# PIC32_NVME.net
KiCad netlist of a schematic drawn in Altium Designer
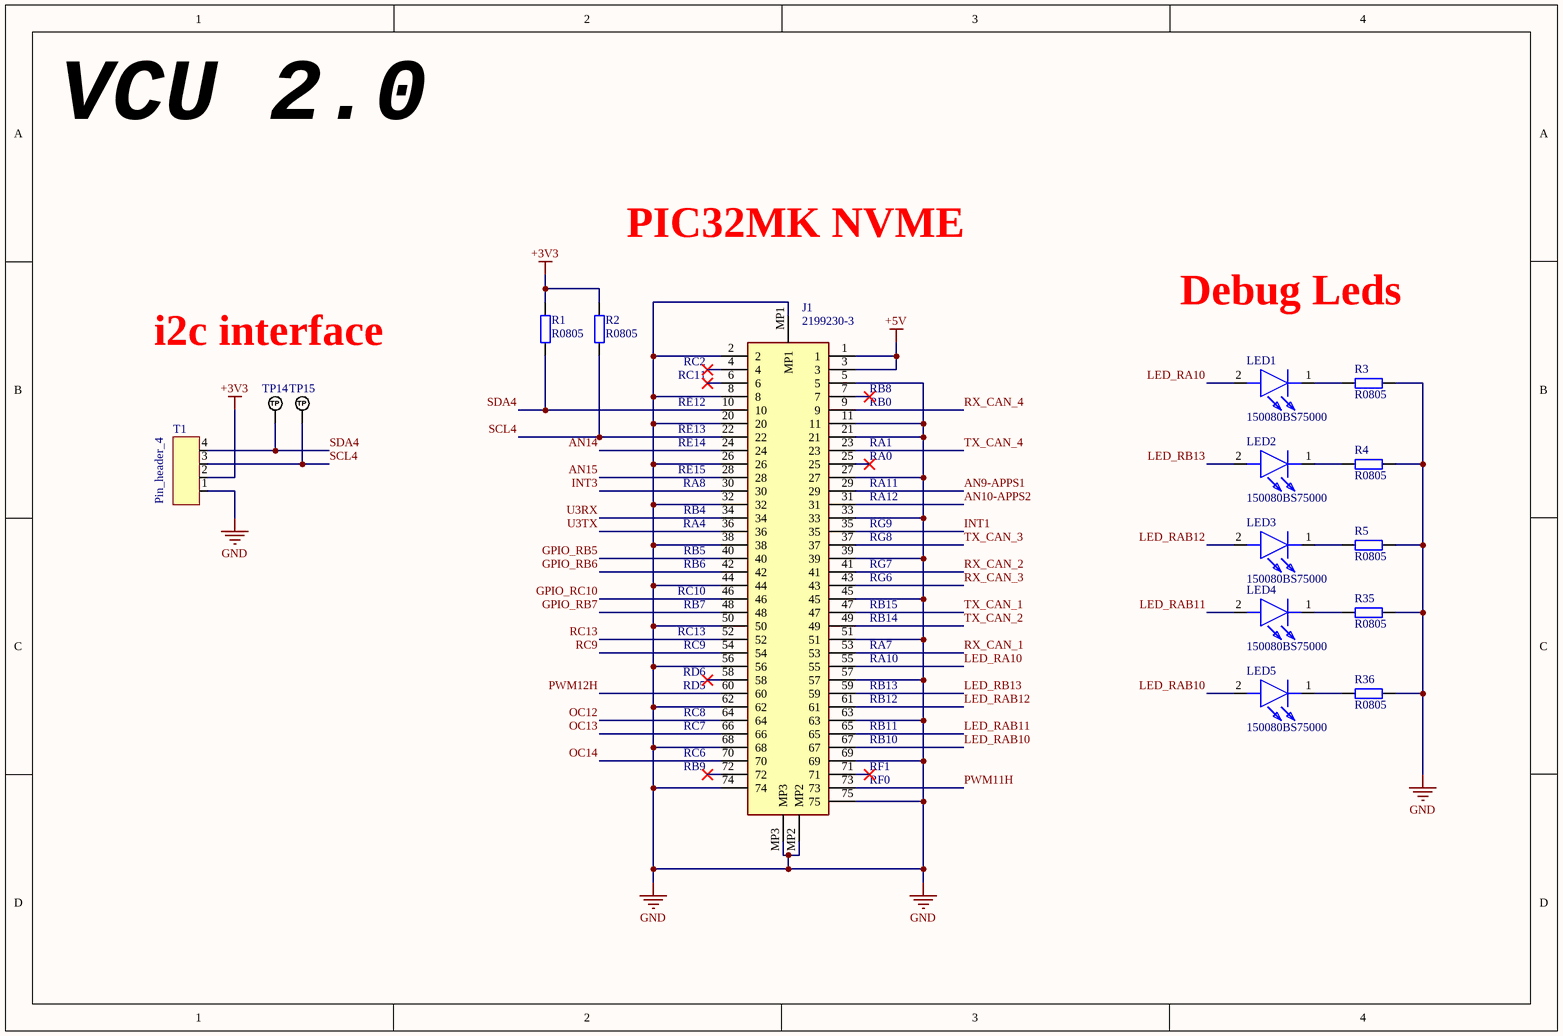
[diagram p0: PIC32_NVME.SchDoc]

(export (version "E")
  (design (tool "Eeschema 10.0.6"))
  (components
    (comp (ref "J1")
      (value "2199230-3")
      (footprint "21992303")
      (description "Connector")
      (fields (field (name "MOUSER PART NUMBER") "571-2199230-3"))
      (libsource (lib "Pedro_Integrated_Library") (part "2199230-3"))
    )
    (comp (ref "LED1")
      (value "150080BS75000")
      (footprint "LEDC2012X80N")
      (description "LED")
      (fields (field (name "MOUSER PART NUMBER") "710-150080BS75000"))
      (libsource (lib "Pedro_Integrated_Library") (part "150080BS75000"))
    )
    (comp (ref "LED2")
      (value "150080BS75000")
      (footprint "LEDC2012X80N")
      (description "LED")
      (fields (field (name "MOUSER PART NUMBER") "710-150080BS75000"))
      (libsource (lib "Pedro_Integrated_Library") (part "150080BS75000"))
    )
    (comp (ref "LED3")
      (value "150080BS75000")
      (footprint "LEDC2012X80N")
      (description "LED")
      (fields (field (name "MOUSER PART NUMBER") "710-150080BS75000"))
      (libsource (lib "Pedro_Integrated_Library") (part "150080BS75000"))
    )
    (comp (ref "LED4")
      (value "150080BS75000")
      (footprint "LEDC2012X80N")
      (description "LED")
      (fields (field (name "MOUSER PART NUMBER") "710-150080BS75000"))
      (libsource (lib "Pedro_Integrated_Library") (part "150080BS75000"))
    )
    (comp (ref "LED5")
      (value "150080BS75000")
      (footprint "LEDC2012X80N")
      (description "LED")
      (fields (field (name "MOUSER PART NUMBER") "710-150080BS75000"))
      (libsource (lib "Pedro_Integrated_Library") (part "150080BS75000"))
    )
    (comp (ref "R1")
      (value "R0805")
      (footprint "RES_0805")
      (description "Resistor SMD 0805")
      (libsource (lib "Schematic-Lib-PhilsLab") (part "RES_0805"))
    )
    (comp (ref "R2")
      (value "R0805")
      (footprint "RES_0805")
      (description "Resistor SMD 0805")
      (libsource (lib "Schematic-Lib-PhilsLab") (part "RES_0805"))
    )
    (comp (ref "R3")
      (value "R0805")
      (footprint "RES_0805")
      (description "Resistor SMD 0805")
      (libsource (lib "Schematic-Lib-PhilsLab") (part "RES_0805"))
    )
    (comp (ref "R4")
      (value "R0805")
      (footprint "RES_0805")
      (description "Resistor SMD 0805")
      (libsource (lib "Schematic-Lib-PhilsLab") (part "RES_0805"))
    )
    (comp (ref "R5")
      (value "R0805")
      (footprint "RES_0805")
      (description "Resistor SMD 0805")
      (libsource (lib "Schematic-Lib-PhilsLab") (part "RES_0805"))
    )
    (comp (ref "R35")
      (value "R0805")
      (footprint "RES_0805")
      (description "Resistor SMD 0805")
      (libsource (lib "Schematic-Lib-PhilsLab") (part "RES_0805"))
    )
    (comp (ref "R36")
      (value "R0805")
      (footprint "RES_0805")
      (description "Resistor SMD 0805")
      (libsource (lib "Schematic-Lib-PhilsLab") (part "RES_0805"))
    )
    (comp (ref "T1")
      (value "Pin_header_4")
      (footprint "Pin_header_4")
      (libsource (lib "Pedro_Integrated_Library") (part "Pin_header_4"))
    )
    (comp (ref "TP14")
      (value "TP_NOBOM")
      (footprint "PAD_RND_1MM")
      (description "Test Point Round 1mm (NO BOM)")
      (libsource (lib "Schematic-Lib-PhilsLab") (part "TEST_POINT_RND_1MM"))
    )
    (comp (ref "TP15")
      (value "TP_NOBOM")
      (footprint "PAD_RND_1MM")
      (description "Test Point Round 1mm (NO BOM)")
      (libsource (lib "Schematic-Lib-PhilsLab") (part "TEST_POINT_RND_1MM"))
    )
  )
  (nets
    (net (code "1") (name "+3V3") (class "Default")
      (node (ref "R1") (pin "1") (pinfunction "1_1") (pintype "passive"))
      (node (ref "R2") (pin "1") (pinfunction "1_1") (pintype "passive"))
      (node (ref "T1") (pin "2") (pintype "bidirectional"))
    )
    (net (code "2") (name "+5V") (class "Default")
      (node (ref "J1") (pin "1") (pinfunction "1_1") (pintype "passive"))
      (node (ref "J1") (pin "3") (pinfunction "3_3") (pintype "passive"))
    )
    (net (code "3") (name "/AN9-APPS1") (class "Default")
      (node (ref "J1") (pin "29") (pinfunction "29_29") (pintype "passive"))
    )
    (net (code "4") (name "/AN10-APPS2") (class "Default")
      (node (ref "J1") (pin "31") (pinfunction "31_31") (pintype "passive"))
    )
    (net (code "5") (name "/AN14") (class "Default")
      (node (ref "J1") (pin "24") (pinfunction "24_24") (pintype "passive"))
    )
    (net (code "6") (name "/AN15") (class "Default")
      (node (ref "J1") (pin "28") (pinfunction "28_28") (pintype "passive"))
    )
    (net (code "7") (name "/GPIO_RB5") (class "Default")
      (node (ref "J1") (pin "40") (pinfunction "40_40") (pintype "passive"))
    )
    (net (code "8") (name "/GPIO_RB6") (class "Default")
      (node (ref "J1") (pin "42") (pinfunction "42_42") (pintype "passive"))
    )
    (net (code "9") (name "/GPIO_RB7") (class "Default")
      (node (ref "J1") (pin "48") (pinfunction "48_48") (pintype "passive"))
    )
    (net (code "10") (name "/GPIO_RC10") (class "Default")
      (node (ref "J1") (pin "46") (pinfunction "46_46") (pintype "passive"))
    )
    (net (code "11") (name "/INT1") (class "Default")
      (node (ref "J1") (pin "35") (pinfunction "35_35") (pintype "passive"))
    )
    (net (code "12") (name "/INT3") (class "Default")
      (node (ref "J1") (pin "30") (pinfunction "30_30") (pintype "passive"))
    )
    (net (code "13") (name "/LED_RA10") (class "Default")
      (node (ref "J1") (pin "55") (pinfunction "55_55") (pintype "passive"))
      (node (ref "LED1") (pin "2") (pinfunction "A_2") (pintype "passive"))
    )
    (net (code "14") (name "/LED_RAB10") (class "Default")
      (node (ref "J1") (pin "67") (pinfunction "67_67") (pintype "passive"))
      (node (ref "LED5") (pin "2") (pinfunction "A_2") (pintype "passive"))
    )
    (net (code "15") (name "/LED_RAB11") (class "Default")
      (node (ref "J1") (pin "65") (pinfunction "65_65") (pintype "passive"))
      (node (ref "LED4") (pin "2") (pinfunction "A_2") (pintype "passive"))
    )
    (net (code "16") (name "/LED_RAB12") (class "Default")
      (node (ref "J1") (pin "61") (pinfunction "61_61") (pintype "passive"))
      (node (ref "LED3") (pin "2") (pinfunction "A_2") (pintype "passive"))
    )
    (net (code "17") (name "/LED_RB13") (class "Default")
      (node (ref "J1") (pin "59") (pinfunction "59_59") (pintype "passive"))
      (node (ref "LED2") (pin "2") (pinfunction "A_2") (pintype "passive"))
    )
    (net (code "18") (name "/OC12") (class "Default")
      (node (ref "J1") (pin "64") (pinfunction "64_64") (pintype "passive"))
    )
    (net (code "19") (name "/OC13") (class "Default")
      (node (ref "J1") (pin "66") (pinfunction "66_66") (pintype "passive"))
    )
    (net (code "20") (name "/OC14") (class "Default")
      (node (ref "J1") (pin "70") (pinfunction "70_70") (pintype "passive"))
    )
    (net (code "21") (name "/PWM11H") (class "Default")
      (node (ref "J1") (pin "73") (pinfunction "73_73") (pintype "passive"))
    )
    (net (code "22") (name "/PWM12H") (class "Default")
      (node (ref "J1") (pin "60") (pinfunction "60_60") (pintype "passive"))
    )
    (net (code "23") (name "/RC9") (class "Default")
      (node (ref "J1") (pin "54") (pinfunction "54_54") (pintype "passive"))
    )
    (net (code "24") (name "/RC13") (class "Default")
      (node (ref "J1") (pin "52") (pinfunction "52_52") (pintype "passive"))
    )
    (net (code "25") (name "/RX_CAN_1") (class "Default")
      (node (ref "J1") (pin "53") (pinfunction "53_53") (pintype "passive"))
    )
    (net (code "26") (name "/RX_CAN_2") (class "Default")
      (node (ref "J1") (pin "41") (pinfunction "41_41") (pintype "passive"))
    )
    (net (code "27") (name "/RX_CAN_3") (class "Default")
      (node (ref "J1") (pin "43") (pinfunction "43_43") (pintype "passive"))
    )
    (net (code "28") (name "/RX_CAN_4") (class "Default")
      (node (ref "J1") (pin "9") (pinfunction "9_9") (pintype "passive"))
    )
    (net (code "29") (name "/SCL4") (class "Default")
      (node (ref "J1") (pin "22") (pinfunction "22_22") (pintype "passive"))
      (node (ref "R2") (pin "2") (pinfunction "2_2") (pintype "passive"))
      (node (ref "T1") (pin "3") (pintype "bidirectional"))
      (node (ref "TP15") (pin "1") (pinfunction "TP_1") (pintype "passive"))
    )
    (net (code "30") (name "/SDA4") (class "Default")
      (node (ref "J1") (pin "10") (pinfunction "10_10") (pintype "passive"))
      (node (ref "R1") (pin "2") (pinfunction "2_2") (pintype "passive"))
      (node (ref "T1") (pin "4") (pintype "bidirectional"))
      (node (ref "TP14") (pin "1") (pinfunction "TP_1") (pintype "passive"))
    )
    (net (code "31") (name "/TX_CAN_1") (class "Default")
      (node (ref "J1") (pin "47") (pinfunction "47_47") (pintype "passive"))
    )
    (net (code "32") (name "/TX_CAN_2") (class "Default")
      (node (ref "J1") (pin "49") (pinfunction "49_49") (pintype "passive"))
    )
    (net (code "33") (name "/TX_CAN_3") (class "Default")
      (node (ref "J1") (pin "37") (pinfunction "37_37") (pintype "passive"))
    )
    (net (code "34") (name "/TX_CAN_4") (class "Default")
      (node (ref "J1") (pin "23") (pinfunction "23_23") (pintype "passive"))
    )
    (net (code "35") (name "/U3RX") (class "Default")
      (node (ref "J1") (pin "34") (pinfunction "34_34") (pintype "passive"))
    )
    (net (code "36") (name "/U3TX") (class "Default")
      (node (ref "J1") (pin "36") (pinfunction "36_36") (pintype "passive"))
    )
    (net (code "37") (name "GND") (class "Default")
      (node (ref "J1") (pin "11") (pinfunction "11_11") (pintype "passive"))
      (node (ref "J1") (pin "2") (pinfunction "2_2") (pintype "passive"))
      (node (ref "J1") (pin "20") (pinfunction "20_20") (pintype "passive"))
      (node (ref "J1") (pin "21") (pinfunction "21_21") (pintype "passive"))
      (node (ref "J1") (pin "26") (pinfunction "26_26") (pintype "passive"))
      (node (ref "J1") (pin "27") (pinfunction "27_27") (pintype "passive"))
      (node (ref "J1") (pin "32") (pinfunction "32_32") (pintype "passive"))
      (node (ref "J1") (pin "33") (pinfunction "33_33") (pintype "passive"))
      (node (ref "J1") (pin "38") (pinfunction "38_38") (pintype "passive"))
      (node (ref "J1") (pin "39") (pinfunction "39_39") (pintype "passive"))
      (node (ref "J1") (pin "44") (pinfunction "44_44") (pintype "passive"))
      (node (ref "J1") (pin "45") (pinfunction "45_45") (pintype "passive"))
      (node (ref "J1") (pin "5") (pinfunction "5_5") (pintype "passive"))
      (node (ref "J1") (pin "50") (pinfunction "50_50") (pintype "passive"))
      (node (ref "J1") (pin "51") (pinfunction "51_51") (pintype "passive"))
      (node (ref "J1") (pin "56") (pinfunction "56_56") (pintype "passive"))
      (node (ref "J1") (pin "57") (pinfunction "57_57") (pintype "passive"))
      (node (ref "J1") (pin "62") (pinfunction "62_62") (pintype "passive"))
      (node (ref "J1") (pin "63") (pinfunction "63_63") (pintype "passive"))
      (node (ref "J1") (pin "68") (pinfunction "68_68") (pintype "passive"))
      (node (ref "J1") (pin "69") (pinfunction "69_69") (pintype "passive"))
      (node (ref "J1") (pin "74") (pinfunction "74_74") (pintype "passive"))
      (node (ref "J1") (pin "75") (pinfunction "75_75") (pintype "passive"))
      (node (ref "J1") (pin "8") (pinfunction "8_8") (pintype "passive"))
      (node (ref "J1") (pin "MP1") (pinfunction "MP1_MP1") (pintype "passive"))
      (node (ref "J1") (pin "MP2") (pinfunction "MP2_MP2") (pintype "passive"))
      (node (ref "J1") (pin "MP3") (pinfunction "MP3_MP3") (pintype "passive"))
      (node (ref "R3") (pin "1") (pinfunction "1_1") (pintype "passive"))
      (node (ref "R35") (pin "1") (pinfunction "1_1") (pintype "passive"))
      (node (ref "R36") (pin "1") (pinfunction "1_1") (pintype "passive"))
      (node (ref "R4") (pin "1") (pinfunction "1_1") (pintype "passive"))
      (node (ref "R5") (pin "1") (pinfunction "1_1") (pintype "passive"))
      (node (ref "T1") (pin "1") (pintype "bidirectional"))
    )
    (net (code "38") (name "Net-(LED1-K)") (class "Default")
      (node (ref "LED1") (pin "1") (pinfunction "K_1") (pintype "passive"))
      (node (ref "R3") (pin "2") (pinfunction "2_2") (pintype "passive"))
    )
    (net (code "39") (name "Net-(LED2-K)") (class "Default")
      (node (ref "LED2") (pin "1") (pinfunction "K_1") (pintype "passive"))
      (node (ref "R4") (pin "2") (pinfunction "2_2") (pintype "passive"))
    )
    (net (code "40") (name "Net-(LED3-K)") (class "Default")
      (node (ref "LED3") (pin "1") (pinfunction "K_1") (pintype "passive"))
      (node (ref "R5") (pin "2") (pinfunction "2_2") (pintype "passive"))
    )
    (net (code "41") (name "Net-(LED4-K)") (class "Default")
      (node (ref "LED4") (pin "1") (pinfunction "K_1") (pintype "passive"))
      (node (ref "R35") (pin "2") (pinfunction "2_2") (pintype "passive"))
    )
    (net (code "42") (name "Net-(LED5-K)") (class "Default")
      (node (ref "LED5") (pin "1") (pinfunction "K_1") (pintype "passive"))
      (node (ref "R36") (pin "2") (pinfunction "2_2") (pintype "passive"))
    )
    (net (code "43") (name "unconnected-(J1-Pad4)") (class "Default")
      (node (ref "J1") (pin "4") (pinfunction "4_4") (pintype "passive+no_connect"))
    )
    (net (code "44") (name "unconnected-(J1-Pad6)") (class "Default")
      (node (ref "J1") (pin "6") (pinfunction "6_6") (pintype "passive+no_connect"))
    )
    (net (code "45") (name "unconnected-(J1-Pad7)") (class "Default")
      (node (ref "J1") (pin "7") (pinfunction "7_7") (pintype "passive+no_connect"))
    )
    (net (code "46") (name "unconnected-(J1-Pad25)") (class "Default")
      (node (ref "J1") (pin "25") (pinfunction "25_25") (pintype "passive+no_connect"))
    )
    (net (code "47") (name "unconnected-(J1-Pad58)") (class "Default")
      (node (ref "J1") (pin "58") (pinfunction "58_58") (pintype "passive+no_connect"))
    )
    (net (code "48") (name "unconnected-(J1-Pad71)") (class "Default")
      (node (ref "J1") (pin "71") (pinfunction "71_71") (pintype "passive+no_connect"))
    )
    (net (code "49") (name "unconnected-(J1-Pad72)") (class "Default")
      (node (ref "J1") (pin "72") (pinfunction "72_72") (pintype "passive+no_connect"))
    )
  )
)
